# SSM4.net
KiCad netlist of a schematic drawn in EAGLE
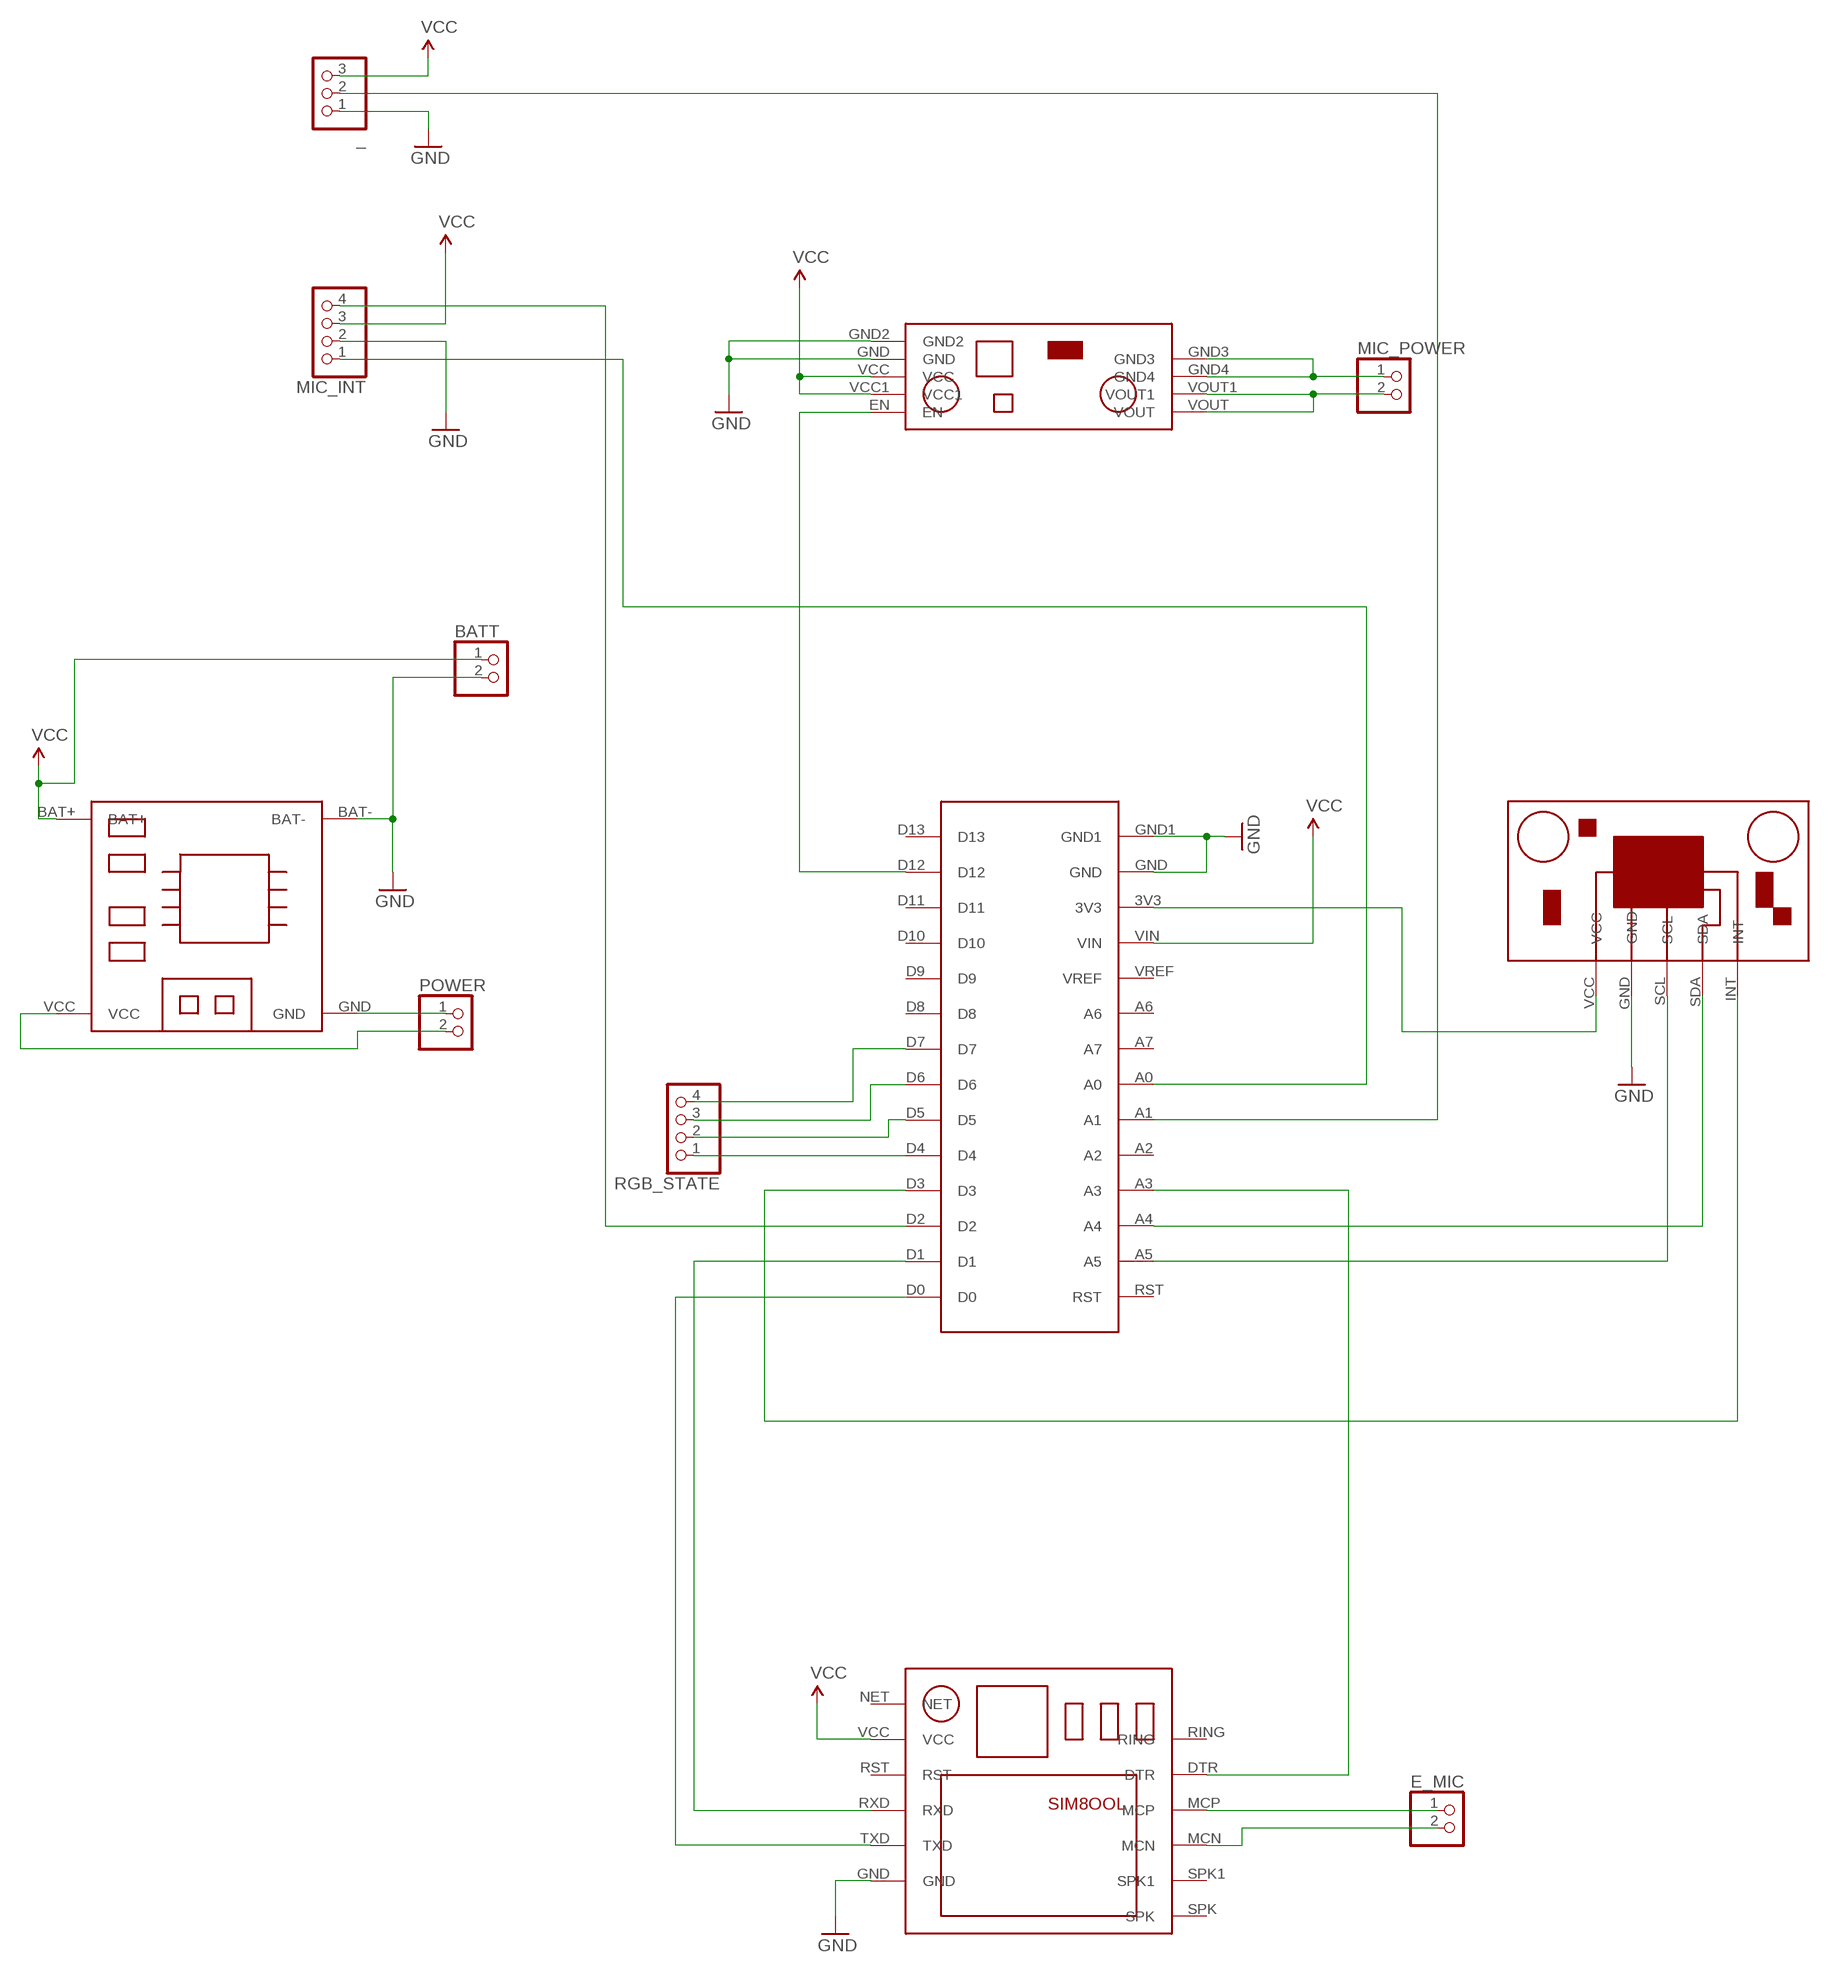
[diagram p0: schematic, sheet 1]

(export (version "E")
  (design (tool "Eeschema 10.0.6"))
  (components
    (comp (ref "BATT")
      (value "PINHD-1X2")
      (footprint "eagle-import:1X02")
      (libsource (lib "eagle-import") (part "PINHD-1X2"))
    )
    (comp (ref "E_MIC")
      (value "PINHD-1X2")
      (footprint "eagle-import:1X02")
      (libsource (lib "eagle-import") (part "PINHD-1X2"))
    )
    (comp (ref "MIC_INT")
      (value "PINHD-1X4")
      (footprint "eagle-import:1X04")
      (libsource (lib "eagle-import") (part "PINHD-1X4"))
    )
    (comp (ref "MIC_POWER")
      (value "PINHD-1X2")
      (footprint "eagle-import:1X02")
      (libsource (lib "eagle-import") (part "PINHD-1X2"))
    )
    (comp (ref "POWER")
      (value "PINHD-1X2")
      (footprint "eagle-import:1X02")
      (libsource (lib "eagle-import") (part "PINHD-1X2"))
    )
    (comp (ref "RGB_STATE")
      (value "PINHD-1X4")
      (footprint "eagle-import:1X04")
      (libsource (lib "eagle-import") (part "PINHD-1X4"))
    )
    (comp (ref "U$1")
      (value "ACELEROMETER")
      (footprint "eagle-import:ACELEROMETER")
      (libsource (lib "eagle-import") (part "ACELEROMETER"))
    )
    (comp (ref "U$2")
      (value "POLOLU_STEP_UP_DOWN")
      (footprint "eagle-import:POLOLU_STEP_UP_DOWN")
      (libsource (lib "eagle-import") (part "POLOLU_STEP_UP_DOWN"))
    )
    (comp (ref "U$3")
      (value "CHARGER")
      (footprint "eagle-import:CHARGER")
      (libsource (lib "eagle-import") (part "CHARGER"))
    )
    (comp (ref "U$4")
      (value "SIM8OOL")
      (footprint "eagle-import:SIM8OOL")
      (libsource (lib "eagle-import") (part "SIM8OOL"))
    )
    (comp (ref "U$5")
      (value "ULTRA_MINI")
      (footprint "eagle-import:ULTRA_MINI")
      (libsource (lib "eagle-import") (part "ULTRA_MINI"))
    )
    (comp (ref "_")
      (value "PINHD-1X3")
      (footprint "eagle-import:1X03")
      (libsource (lib "eagle-import") (part "PINHD-1X3"))
    )
  )
  (nets
    (net (code "1") (name "GND") (class "Default")
      (node (ref "BATT") (pin "2") (pinfunction "2_2") (pintype "passive"))
      (node (ref "MIC_INT") (pin "2") (pinfunction "2_2") (pintype "passive"))
      (node (ref "U$1") (pin "GND") (pinfunction "GND_GND") (pintype "bidirectional"))
      (node (ref "U$2") (pin "GND") (pinfunction "GND_GND") (pintype "bidirectional"))
      (node (ref "U$2") (pin "GND2") (pinfunction "GND2_GND2") (pintype "bidirectional"))
      (node (ref "U$3") (pin "BAT-") (pinfunction "BAT-_BAT-") (pintype "bidirectional"))
      (node (ref "U$4") (pin "GND") (pinfunction "GND_GND") (pintype "bidirectional"))
      (node (ref "U$5") (pin "GND") (pinfunction "GND_GND") (pintype "bidirectional"))
      (node (ref "U$5") (pin "GND1") (pinfunction "GND1_GND1") (pintype "bidirectional"))
      (node (ref "_") (pin "1") (pinfunction "1_1") (pintype "passive"))
    )
    (net (code "2") (name "Net-(E_MIC-Pad1)") (class "Default")
      (node (ref "E_MIC") (pin "1") (pinfunction "1_1") (pintype "passive"))
      (node (ref "U$4") (pin "MCP") (pinfunction "MCP_MCP") (pintype "bidirectional"))
    )
    (net (code "3") (name "Net-(E_MIC-Pad2)") (class "Default")
      (node (ref "E_MIC") (pin "2") (pinfunction "2_2") (pintype "passive"))
      (node (ref "U$4") (pin "MCN") (pinfunction "MCN_MCN") (pintype "bidirectional"))
    )
    (net (code "4") (name "Net-(MIC_INT-Pad1)") (class "Default")
      (node (ref "MIC_INT") (pin "1") (pinfunction "1_1") (pintype "passive"))
      (node (ref "U$5") (pin "A0") (pinfunction "A0_A0") (pintype "bidirectional"))
    )
    (net (code "5") (name "Net-(MIC_INT-Pad4)") (class "Default")
      (node (ref "MIC_INT") (pin "4") (pinfunction "4_4") (pintype "passive"))
      (node (ref "U$5") (pin "D2") (pinfunction "D2_D2") (pintype "bidirectional"))
    )
    (net (code "6") (name "Net-(MIC_POWER-Pad1)") (class "Default")
      (node (ref "MIC_POWER") (pin "1") (pinfunction "1_1") (pintype "passive"))
      (node (ref "U$2") (pin "GND3") (pinfunction "GND3_GND3") (pintype "bidirectional"))
      (node (ref "U$2") (pin "GND4") (pinfunction "GND4_GND4") (pintype "bidirectional"))
    )
    (net (code "7") (name "Net-(MIC_POWER-Pad2)") (class "Default")
      (node (ref "MIC_POWER") (pin "2") (pinfunction "2_2") (pintype "passive"))
      (node (ref "U$2") (pin "VOUT") (pinfunction "VOUT_VOUT") (pintype "bidirectional"))
      (node (ref "U$2") (pin "VOUT1") (pinfunction "VOUT1_VOUT1") (pintype "bidirectional"))
    )
    (net (code "8") (name "Net-(POWER-Pad1)") (class "Default")
      (node (ref "POWER") (pin "1") (pinfunction "1_1") (pintype "passive"))
      (node (ref "U$3") (pin "GND") (pinfunction "GND_GND") (pintype "bidirectional"))
    )
    (net (code "9") (name "Net-(POWER-Pad2)") (class "Default")
      (node (ref "POWER") (pin "2") (pinfunction "2_2") (pintype "passive"))
      (node (ref "U$3") (pin "VCC") (pinfunction "VCC_VCC") (pintype "bidirectional"))
    )
    (net (code "10") (name "Net-(RGB_STATE-Pad1)") (class "Default")
      (node (ref "RGB_STATE") (pin "1") (pinfunction "1_1") (pintype "passive"))
      (node (ref "U$5") (pin "D4") (pinfunction "D4_D4") (pintype "bidirectional"))
    )
    (net (code "11") (name "Net-(RGB_STATE-Pad2)") (class "Default")
      (node (ref "RGB_STATE") (pin "2") (pinfunction "2_2") (pintype "passive"))
      (node (ref "U$5") (pin "D5") (pinfunction "D5_D5") (pintype "bidirectional"))
    )
    (net (code "12") (name "Net-(RGB_STATE-Pad3)") (class "Default")
      (node (ref "RGB_STATE") (pin "3") (pinfunction "3_3") (pintype "passive"))
      (node (ref "U$5") (pin "D6") (pinfunction "D6_D6") (pintype "bidirectional"))
    )
    (net (code "13") (name "Net-(RGB_STATE-Pad4)") (class "Default")
      (node (ref "RGB_STATE") (pin "4") (pinfunction "4_4") (pintype "passive"))
      (node (ref "U$5") (pin "D7") (pinfunction "D7_D7") (pintype "bidirectional"))
    )
    (net (code "14") (name "Net-(U$1-PadINT)") (class "Default")
      (node (ref "U$1") (pin "INT") (pinfunction "INT_INT") (pintype "bidirectional"))
      (node (ref "U$5") (pin "D3") (pinfunction "D3_D3") (pintype "bidirectional"))
    )
    (net (code "15") (name "Net-(U$1-PadSCL)") (class "Default")
      (node (ref "U$1") (pin "SCL") (pinfunction "SCL_SCL") (pintype "bidirectional"))
      (node (ref "U$5") (pin "A5") (pinfunction "A5_A5") (pintype "bidirectional"))
    )
    (net (code "16") (name "Net-(U$1-PadSDA)") (class "Default")
      (node (ref "U$1") (pin "SDA") (pinfunction "SDA_SDA") (pintype "bidirectional"))
      (node (ref "U$5") (pin "A4") (pinfunction "A4_A4") (pintype "bidirectional"))
    )
    (net (code "17") (name "Net-(U$1-PadVCC)") (class "Default")
      (node (ref "U$1") (pin "VCC") (pinfunction "VCC_VCC") (pintype "bidirectional"))
      (node (ref "U$5") (pin "3V3") (pinfunction "3V3_3V3") (pintype "bidirectional"))
    )
    (net (code "18") (name "Net-(U$2-PadEN)") (class "Default")
      (node (ref "U$2") (pin "EN") (pinfunction "EN_EN") (pintype "bidirectional"))
      (node (ref "U$5") (pin "D12") (pinfunction "D12_D12") (pintype "bidirectional"))
    )
    (net (code "19") (name "Net-(U$4-PadDTR)") (class "Default")
      (node (ref "U$4") (pin "DTR") (pinfunction "DTR_DTR") (pintype "bidirectional"))
      (node (ref "U$5") (pin "A3") (pinfunction "A3_A3") (pintype "bidirectional"))
    )
    (net (code "20") (name "Net-(U$4-PadRXD)") (class "Default")
      (node (ref "U$4") (pin "RXD") (pinfunction "RXD_RXD") (pintype "bidirectional"))
      (node (ref "U$5") (pin "D1") (pinfunction "D1_D1") (pintype "bidirectional"))
    )
    (net (code "21") (name "Net-(U$4-PadTXD)") (class "Default")
      (node (ref "U$4") (pin "TXD") (pinfunction "TXD_TXD") (pintype "bidirectional"))
      (node (ref "U$5") (pin "D0") (pinfunction "D0_D0") (pintype "bidirectional"))
    )
    (net (code "22") (name "Net-(U$5-PadA1)") (class "Default")
      (node (ref "U$5") (pin "A1") (pinfunction "A1_A1") (pintype "bidirectional"))
      (node (ref "_") (pin "2") (pinfunction "2_2") (pintype "passive"))
    )
    (net (code "23") (name "VCC") (class "Default")
      (node (ref "BATT") (pin "1") (pinfunction "1_1") (pintype "passive"))
      (node (ref "MIC_INT") (pin "3") (pinfunction "3_3") (pintype "passive"))
      (node (ref "U$2") (pin "VCC") (pinfunction "VCC_VCC") (pintype "bidirectional"))
      (node (ref "U$2") (pin "VCC1") (pinfunction "VCC1_VCC1") (pintype "bidirectional"))
      (node (ref "U$3") (pin "BAT+") (pinfunction "BAT+_BAT+") (pintype "bidirectional"))
      (node (ref "U$4") (pin "VCC") (pinfunction "VCC_VCC") (pintype "bidirectional"))
      (node (ref "U$5") (pin "VIN") (pinfunction "VIN_VIN") (pintype "bidirectional"))
      (node (ref "_") (pin "3") (pinfunction "3_3") (pintype "passive"))
    )
    (net (code "24") (name "unconnected-(U$4-PadNET)") (class "Default")
      (node (ref "U$4") (pin "NET") (pinfunction "NET_NET") (pintype "bidirectional"))
    )
    (net (code "25") (name "unconnected-(U$4-PadRING)") (class "Default")
      (node (ref "U$4") (pin "RING") (pinfunction "RING_RING") (pintype "bidirectional"))
    )
    (net (code "26") (name "unconnected-(U$4-PadRST)") (class "Default")
      (node (ref "U$4") (pin "RST") (pinfunction "RST_RST") (pintype "bidirectional"))
    )
    (net (code "27") (name "unconnected-(U$4-PadSPK)") (class "Default")
      (node (ref "U$4") (pin "SPK") (pinfunction "SPK_SPK") (pintype "bidirectional"))
    )
    (net (code "28") (name "unconnected-(U$4-PadSPK1)") (class "Default")
      (node (ref "U$4") (pin "SPK1") (pinfunction "SPK1_SPK1") (pintype "bidirectional"))
    )
    (net (code "29") (name "unconnected-(U$5-PadA2)") (class "Default")
      (node (ref "U$5") (pin "A2") (pinfunction "A2_A2") (pintype "bidirectional"))
    )
    (net (code "30") (name "unconnected-(U$5-PadA6)") (class "Default")
      (node (ref "U$5") (pin "A6") (pinfunction "A6_A6") (pintype "bidirectional"))
    )
    (net (code "31") (name "unconnected-(U$5-PadA7)") (class "Default")
      (node (ref "U$5") (pin "A7") (pinfunction "A7_A7") (pintype "bidirectional"))
    )
    (net (code "32") (name "unconnected-(U$5-PadD8)") (class "Default")
      (node (ref "U$5") (pin "D8") (pinfunction "D8_D8") (pintype "bidirectional"))
    )
    (net (code "33") (name "unconnected-(U$5-PadD9)") (class "Default")
      (node (ref "U$5") (pin "D9") (pinfunction "D9_D9") (pintype "bidirectional"))
    )
    (net (code "34") (name "unconnected-(U$5-PadD10)") (class "Default")
      (node (ref "U$5") (pin "D10") (pinfunction "D10_D10") (pintype "bidirectional"))
    )
    (net (code "35") (name "unconnected-(U$5-PadD11)") (class "Default")
      (node (ref "U$5") (pin "D11") (pinfunction "D11_D11") (pintype "bidirectional"))
    )
    (net (code "36") (name "unconnected-(U$5-PadD13)") (class "Default")
      (node (ref "U$5") (pin "D13") (pinfunction "D13_D13") (pintype "bidirectional"))
    )
    (net (code "37") (name "unconnected-(U$5-PadRST)") (class "Default")
      (node (ref "U$5") (pin "RST") (pinfunction "RST_RST") (pintype "bidirectional"))
    )
    (net (code "38") (name "unconnected-(U$5-PadVREF)") (class "Default")
      (node (ref "U$5") (pin "VREF") (pinfunction "VREF_VREF") (pintype "bidirectional"))
    )
  )
)
